# MCU.net
KiCad netlist of a schematic drawn in Altium Designer
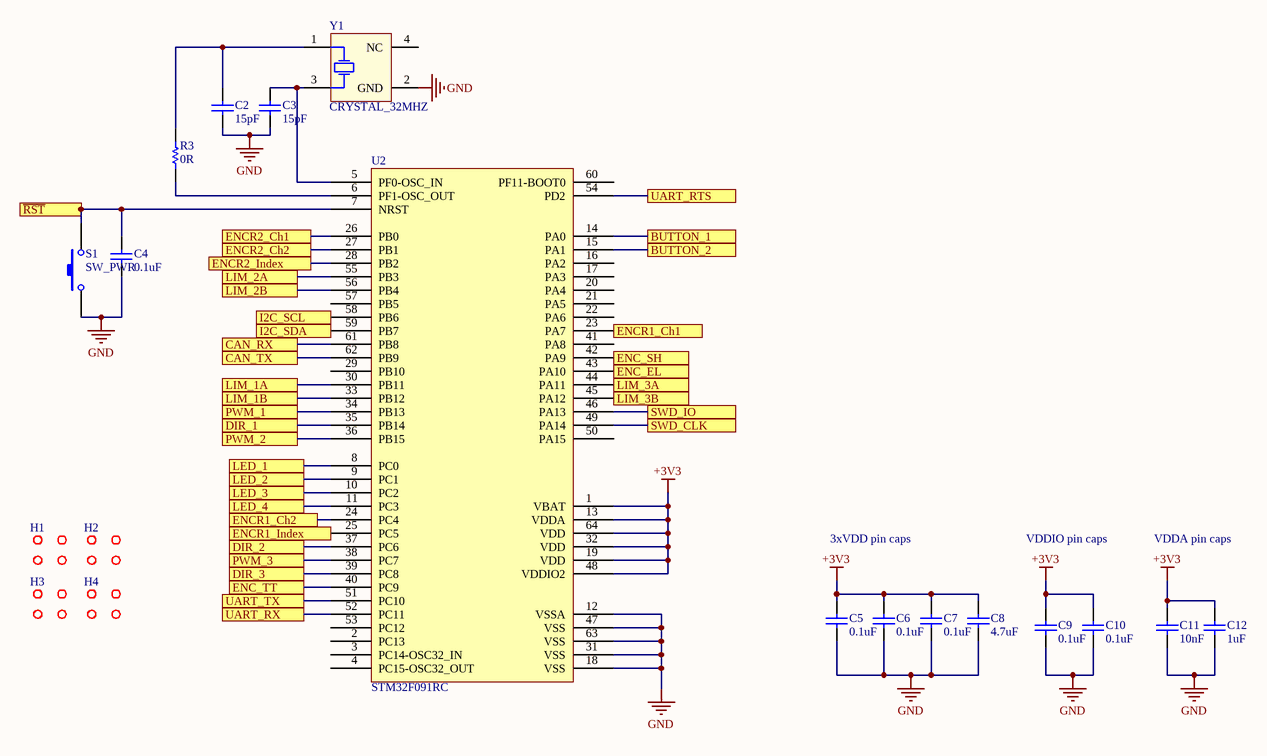
[diagram p0: MCU.SchDoc]

(export (version "E")
  (design (tool "Eeschema 10.0.6"))
  (components
    (comp (ref "C2")
      (value "15pF")
      (footprint "CAPC0603(1608)55_N")
      (description "CAP CER 15PF 250V NPO 0603")
      (fields (field (name "MANUFACTURER") "Yageo") (field (name "MPN") "AC0603JRNPOYBN150"))
      (libsource (lib "UWRT_Schematic_Library_2019") (part "CAP_15pF_0603"))
    )
    (comp (ref "C3")
      (value "15pF")
      (footprint "CAPC0603(1608)55_N")
      (description "CAP CER 15PF 250V NPO 0603")
      (fields (field (name "MANUFACTURER") "Yageo") (field (name "MPN") "AC0603JRNPOYBN150"))
      (libsource (lib "UWRT_Schematic_Library_2019") (part "CAP_15pF_0603"))
    )
    (comp (ref "C4")
      (value "0.1uF")
      (footprint "CAPC0603(1608)55_N")
      (description "CAP CER 0.1UF 16V X7R 0603")
      (fields (field (name "MANUFACTURER") "Yageo") (field (name "MPN") "CC0603KRX7R7BB104"))
      (libsource (lib "UWRT_Schematic_Library_2019") (part "CAP_0.1uF_16V_0603"))
    )
    (comp (ref "C5")
      (value "0.1uF")
      (footprint "CAPC0603(1608)55_N")
      (description "CAP CER 0.1UF 16V X7R 0603")
      (fields (field (name "MANUFACTURER") "Yageo") (field (name "MPN") "CC0603KRX7R7BB104"))
      (libsource (lib "UWRT_Schematic_Library_2019") (part "CAP_0.1uF_16V_0603"))
    )
    (comp (ref "C6")
      (value "0.1uF")
      (footprint "CAPC0603(1608)55_N")
      (description "CAP CER 0.1UF 16V X7R 0603")
      (fields (field (name "MANUFACTURER") "Yageo") (field (name "MPN") "CC0603KRX7R7BB104"))
      (libsource (lib "UWRT_Schematic_Library_2019") (part "CAP_0.1uF_16V_0603"))
    )
    (comp (ref "C7")
      (value "0.1uF")
      (footprint "CAPC0603(1608)55_N")
      (description "CAP CER 0.1UF 16V X7R 0603")
      (fields (field (name "MANUFACTURER") "Yageo") (field (name "MPN") "CC0603KRX7R7BB104"))
      (libsource (lib "UWRT_Schematic_Library_2019") (part "CAP_0.1uF_16V_0603"))
    )
    (comp (ref "C8")
      (value "4.7uF")
      (footprint "CAPC0603(1608)55_N")
      (description "CAP CER 4.7UF 6.3V X5R 0603")
      (fields (field (name "MANUFACTURER") "Yageo") (field (name "MPN") "CC0603KRX5R5BB475"))
      (libsource (lib "UWRT_Schematic_Library_2019") (part "CAP_4.7uF_0603"))
    )
    (comp (ref "C9")
      (value "0.1uF")
      (footprint "CAPC0603(1608)55_N")
      (description "CAP CER 0.1UF 16V X7R 0603")
      (fields (field (name "MANUFACTURER") "Yageo") (field (name "MPN") "CC0603KRX7R7BB104"))
      (libsource (lib "UWRT_Schematic_Library_2019") (part "CAP_0.1uF_16V_0603"))
    )
    (comp (ref "C10")
      (value "0.1uF")
      (footprint "CAPC0603(1608)55_N")
      (description "CAP CER 0.1UF 16V X7R 0603")
      (fields (field (name "MANUFACTURER") "Yageo") (field (name "MPN") "CC0603KRX7R7BB104"))
      (libsource (lib "UWRT_Schematic_Library_2019") (part "CAP_0.1uF_16V_0603"))
    )
    (comp (ref "C11")
      (value "10nF")
      (footprint "CAPC0603(1608)55_N")
      (description "CAP CER 10000PF 16V X7R 0603")
      (fields (field (name "MANUFACTURER") "Yageo") (field (name "MPN") "CC0603KRX7R7BB103"))
      (libsource (lib "UWRT_Schematic_Library_2019") (part "CAP_10nF_0603"))
    )
    (comp (ref "C12")
      (value "1uF")
      (footprint "CAPC0603(1608)55_N")
      (description "CAP CER 1UF 16V Y5V 0603")
      (fields (field (name "MANUFACTURER") "Yageo") (field (name "MPN") "CC0603ZRY5V7BB105"))
      (libsource (lib "UWRT_Schematic_Library_2019") (part "CAP_1uF_16V_0603"))
    )
    (comp (ref "H1")
      (value "MOUNTING_HOLES")
      (footprint "MOUNTING_HOLE")
      (description "6cm x 6cm")
      (libsource (lib "UWRT_Schematic_Library_2019") (part "MOUNTING_HOLES"))
    )
    (comp (ref "H2")
      (value "MOUNTING_HOLES")
      (footprint "MOUNTING_HOLE")
      (description "6cm x 6cm")
      (libsource (lib "UWRT_Schematic_Library_2019") (part "MOUNTING_HOLES"))
    )
    (comp (ref "H3")
      (value "MOUNTING_HOLES")
      (footprint "MOUNTING_HOLE")
      (description "6cm x 6cm")
      (libsource (lib "UWRT_Schematic_Library_2019") (part "MOUNTING_HOLES"))
    )
    (comp (ref "H4")
      (value "MOUNTING_HOLES")
      (footprint "MOUNTING_HOLE")
      (description "6cm x 6cm")
      (libsource (lib "UWRT_Schematic_Library_2019") (part "MOUNTING_HOLES"))
    )
    (comp (ref "R3")
      (value "0R")
      (footprint "RESC0603(1608)_N")
      (description "RES SMD 0 OHM JUMPER 1/10W 0603")
      (fields (field (name "MANUFACTURER") "Yageo") (field (name "MPN") "RC0603JR-070RL"))
      (libsource (lib "UWRT_Schematic_Library_2019") (part "RES_0R_0603"))
    )
    (comp (ref "S1")
      (value "SW_PWR")
      (footprint "PTS830GM140")
      (description "Power Switch (Red)")
      (fields
        (field (name "MPN") "PTS830GM140 SMTR LFS")
        (field (name "DIGIKEY PART NUMBER") "CKN10587CT-ND")
      )
      (libsource (lib "UWRT_Schematic_Library_2019") (part "SW_PWR"))
    )
    (comp (ref "U2")
      (value "STM32F091RC")
      (footprint "UWRT_Footprint_Library_2019:STM_LQFP64_N")
      (fields
        (field (name "MANUFACTURER") "STMicroelectronics")
        (field (name "DIGIKEY PART NUMBER") "497-15167-ND")
      )
      (libsource (lib "UWRT_Schematic_Library_2019") (part "STM32F091RC"))
    )
    (comp (ref "Y1")
      (value "CRYSTAL_32MHZ")
      (footprint "AVX-CX2520DB32000D0GEJZ1-4_V")
      (description "CRYSTAL 32MHZ 8PF SMD")
      (fields
        (field (name "MANUFACTURER") "Kyocera International Inc. Electronic Components")
        (field (name "MPN") "CX2520DB32000D0GPSC1")
      )
      (libsource (lib "UWRT_Schematic_Library_2019") (part "CRYSTAL_32MHZ"))
    )
  )
  (nets
    (net (code "1") (name "+3V3") (class "Default")
      (node (ref "C10") (pin "2") (pinfunction "2_2") (pintype "passive"))
      (node (ref "C11") (pin "2") (pinfunction "2_2") (pintype "passive"))
      (node (ref "C12") (pin "2") (pinfunction "2_2") (pintype "passive"))
      (node (ref "C5") (pin "2") (pinfunction "2_2") (pintype "passive"))
      (node (ref "C6") (pin "2") (pinfunction "2_2") (pintype "passive"))
      (node (ref "C7") (pin "2") (pinfunction "2_2") (pintype "passive"))
      (node (ref "C8") (pin "2") (pinfunction "2_2") (pintype "passive"))
      (node (ref "C9") (pin "2") (pinfunction "2_2") (pintype "passive"))
      (node (ref "U2") (pin "1") (pinfunction "VBAT_1") (pintype "passive"))
      (node (ref "U2") (pin "13") (pinfunction "VDDA_13") (pintype "passive"))
      (node (ref "U2") (pin "19") (pinfunction "VDD_19") (pintype "passive"))
      (node (ref "U2") (pin "32") (pinfunction "VDD_32") (pintype "passive"))
      (node (ref "U2") (pin "48") (pinfunction "VDDIO2_48") (pintype "passive"))
      (node (ref "U2") (pin "64") (pinfunction "VDD_64") (pintype "passive"))
    )
    (net (code "2") (name "/BUTTON_1") (class "Default")
      (node (ref "U2") (pin "14") (pinfunction "PA0_14") (pintype "passive"))
    )
    (net (code "3") (name "/BUTTON_2") (class "Default")
      (node (ref "U2") (pin "15") (pinfunction "PA1_15") (pintype "passive"))
    )
    (net (code "4") (name "/CAN_RX") (class "Default")
      (node (ref "U2") (pin "61") (pinfunction "PB8_61") (pintype "passive"))
    )
    (net (code "5") (name "/CAN_TX") (class "Default")
      (node (ref "U2") (pin "62") (pinfunction "PB9_62") (pintype "passive"))
    )
    (net (code "6") (name "/DIR_1") (class "Default")
      (node (ref "U2") (pin "35") (pinfunction "PB14_35") (pintype "passive"))
    )
    (net (code "7") (name "/DIR_2") (class "Default")
      (node (ref "U2") (pin "37") (pinfunction "PC6_37") (pintype "passive"))
    )
    (net (code "8") (name "/DIR_3") (class "Default")
      (node (ref "U2") (pin "39") (pinfunction "PC8_39") (pintype "passive"))
    )
    (net (code "9") (name "/ENCR1_Ch1") (class "Default")
      (node (ref "U2") (pin "23") (pinfunction "PA7_23") (pintype "passive"))
    )
    (net (code "10") (name "/ENCR1_Ch2") (class "Default")
      (node (ref "U2") (pin "24") (pinfunction "PC4_24") (pintype "passive"))
    )
    (net (code "11") (name "/ENCR1_Index") (class "Default")
      (node (ref "U2") (pin "25") (pinfunction "PC5_25") (pintype "passive"))
    )
    (net (code "12") (name "/ENCR2_Ch1") (class "Default")
      (node (ref "U2") (pin "26") (pinfunction "PB0_26") (pintype "passive"))
    )
    (net (code "13") (name "/ENCR2_Ch2") (class "Default")
      (node (ref "U2") (pin "27") (pinfunction "PB1_27") (pintype "passive"))
    )
    (net (code "14") (name "/ENCR2_Index") (class "Default")
      (node (ref "U2") (pin "28") (pinfunction "PB2_28") (pintype "passive"))
    )
    (net (code "15") (name "/ENC_EL") (class "Default")
      (node (ref "U2") (pin "43") (pinfunction "PA10_43") (pintype "passive"))
    )
    (net (code "16") (name "/ENC_SH") (class "Default")
      (node (ref "U2") (pin "42") (pinfunction "PA9_42") (pintype "passive"))
    )
    (net (code "17") (name "/ENC_TT") (class "Default")
      (node (ref "U2") (pin "40") (pinfunction "PC9_40") (pintype "passive"))
    )
    (net (code "18") (name "/I2C_SCL") (class "Default")
      (node (ref "U2") (pin "58") (pinfunction "PB6_58") (pintype "passive"))
    )
    (net (code "19") (name "/I2C_SDA") (class "Default")
      (node (ref "U2") (pin "59") (pinfunction "PB7_59") (pintype "passive"))
    )
    (net (code "20") (name "/LED_1") (class "Default")
      (node (ref "U2") (pin "8") (pinfunction "PC0_8") (pintype "passive"))
    )
    (net (code "21") (name "/LED_2") (class "Default")
      (node (ref "U2") (pin "9") (pinfunction "PC1_9") (pintype "passive"))
    )
    (net (code "22") (name "/LED_3") (class "Default")
      (node (ref "U2") (pin "10") (pinfunction "PC2_10") (pintype "passive"))
    )
    (net (code "23") (name "/LED_4") (class "Default")
      (node (ref "U2") (pin "11") (pinfunction "PC3_11") (pintype "passive"))
    )
    (net (code "24") (name "/LIM_1A") (class "Default")
      (node (ref "U2") (pin "30") (pinfunction "PB11_30") (pintype "passive"))
    )
    (net (code "25") (name "/LIM_1B") (class "Default")
      (node (ref "U2") (pin "33") (pinfunction "PB12_33") (pintype "passive"))
    )
    (net (code "26") (name "/LIM_2A") (class "Default")
      (node (ref "U2") (pin "55") (pinfunction "PB3_55") (pintype "passive"))
    )
    (net (code "27") (name "/LIM_2B") (class "Default")
      (node (ref "U2") (pin "56") (pinfunction "PB4_56") (pintype "passive"))
    )
    (net (code "28") (name "/LIM_3A") (class "Default")
      (node (ref "U2") (pin "44") (pinfunction "PA11_44") (pintype "passive"))
    )
    (net (code "29") (name "/LIM_3B") (class "Default")
      (node (ref "U2") (pin "45") (pinfunction "PA12_45") (pintype "passive"))
    )
    (net (code "30") (name "/PWM_1") (class "Default")
      (node (ref "U2") (pin "34") (pinfunction "PB13_34") (pintype "passive"))
    )
    (net (code "31") (name "/PWM_2") (class "Default")
      (node (ref "U2") (pin "36") (pinfunction "PB15_36") (pintype "passive"))
    )
    (net (code "32") (name "/PWM_3") (class "Default")
      (node (ref "U2") (pin "38") (pinfunction "PC7_38") (pintype "passive"))
    )
    (net (code "33") (name "/SWD_CLK") (class "Default")
      (node (ref "U2") (pin "49") (pinfunction "PA14_49") (pintype "passive"))
    )
    (net (code "34") (name "/SWD_IO") (class "Default")
      (node (ref "U2") (pin "46") (pinfunction "PA13_46") (pintype "passive"))
    )
    (net (code "35") (name "/UART_RTS") (class "Default")
      (node (ref "U2") (pin "54") (pinfunction "PD2_54") (pintype "passive"))
    )
    (net (code "36") (name "/UART_RX") (class "Default")
      (node (ref "U2") (pin "52") (pinfunction "PC11_52") (pintype "passive"))
    )
    (net (code "37") (name "/UART_TX") (class "Default")
      (node (ref "U2") (pin "51") (pinfunction "PC10_51") (pintype "passive"))
    )
    (net (code "38") (name "/~{RST}") (class "Default")
      (node (ref "C4") (pin "2") (pinfunction "2_2") (pintype "passive"))
      (node (ref "S1") (pin "2") (pinfunction "2_2") (pintype "passive"))
      (node (ref "U2") (pin "7") (pinfunction "NRST_7") (pintype "passive"))
    )
    (net (code "39") (name "GND") (class "Default")
      (node (ref "C10") (pin "1") (pinfunction "1_1") (pintype "passive"))
      (node (ref "C11") (pin "1") (pinfunction "1_1") (pintype "passive"))
      (node (ref "C12") (pin "1") (pinfunction "1_1") (pintype "passive"))
      (node (ref "C2") (pin "1") (pinfunction "1_1") (pintype "passive"))
      (node (ref "C3") (pin "1") (pinfunction "1_1") (pintype "passive"))
      (node (ref "C4") (pin "1") (pinfunction "1_1") (pintype "passive"))
      (node (ref "C5") (pin "1") (pinfunction "1_1") (pintype "passive"))
      (node (ref "C6") (pin "1") (pinfunction "1_1") (pintype "passive"))
      (node (ref "C7") (pin "1") (pinfunction "1_1") (pintype "passive"))
      (node (ref "C8") (pin "1") (pinfunction "1_1") (pintype "passive"))
      (node (ref "C9") (pin "1") (pinfunction "1_1") (pintype "passive"))
      (node (ref "S1") (pin "1") (pinfunction "1_1") (pintype "passive"))
      (node (ref "U2") (pin "12") (pinfunction "VSSA_12") (pintype "passive"))
      (node (ref "U2") (pin "18") (pinfunction "VSS_18") (pintype "passive"))
      (node (ref "U2") (pin "31") (pinfunction "VSS_31") (pintype "passive"))
      (node (ref "U2") (pin "47") (pinfunction "VSS_47") (pintype "passive"))
      (node (ref "U2") (pin "63") (pinfunction "VSS_63") (pintype "passive"))
      (node (ref "Y1") (pin "2") (pinfunction "GND_2") (pintype "power_in"))
    )
    (net (code "40") (name "Net-(C2-Pad2)") (class "Default")
      (node (ref "C2") (pin "2") (pinfunction "2_2") (pintype "passive"))
      (node (ref "R3") (pin "2") (pinfunction "2_2") (pintype "passive"))
      (node (ref "Y1") (pin "1") (pinfunction "HOT_1") (pintype "passive"))
    )
    (net (code "41") (name "Net-(U2-PF0-OSC_IN)") (class "Default")
      (node (ref "C3") (pin "2") (pinfunction "2_2") (pintype "passive"))
      (node (ref "U2") (pin "5") (pinfunction "PF0-OSC_IN_5") (pintype "passive"))
      (node (ref "Y1") (pin "3") (pinfunction "HOT_3") (pintype "passive"))
    )
    (net (code "42") (name "Net-(U2-PF1-OSC_OUT)") (class "Default")
      (node (ref "R3") (pin "1") (pinfunction "1_1") (pintype "passive"))
      (node (ref "U2") (pin "6") (pinfunction "PF1-OSC_OUT_6") (pintype "passive"))
    )
    (net (code "43") (name "unconnected-(U2-PA2-Pad16)") (class "Default")
      (node (ref "U2") (pin "16") (pinfunction "PA2_16") (pintype "passive"))
    )
    (net (code "44") (name "unconnected-(U2-PA3-Pad17)") (class "Default")
      (node (ref "U2") (pin "17") (pinfunction "PA3_17") (pintype "passive"))
    )
    (net (code "45") (name "unconnected-(U2-PA4-Pad20)") (class "Default")
      (node (ref "U2") (pin "20") (pinfunction "PA4_20") (pintype "passive"))
    )
    (net (code "46") (name "unconnected-(U2-PA5-Pad21)") (class "Default")
      (node (ref "U2") (pin "21") (pinfunction "PA5_21") (pintype "passive"))
    )
    (net (code "47") (name "unconnected-(U2-PA6-Pad22)") (class "Default")
      (node (ref "U2") (pin "22") (pinfunction "PA6_22") (pintype "passive"))
    )
    (net (code "48") (name "unconnected-(U2-PA8-Pad41)") (class "Default")
      (node (ref "U2") (pin "41") (pinfunction "PA8_41") (pintype "passive"))
    )
    (net (code "49") (name "unconnected-(U2-PA15-Pad50)") (class "Default")
      (node (ref "U2") (pin "50") (pinfunction "PA15_50") (pintype "passive"))
    )
    (net (code "50") (name "unconnected-(U2-PB5-Pad57)") (class "Default")
      (node (ref "U2") (pin "57") (pinfunction "PB5_57") (pintype "passive"))
    )
    (net (code "51") (name "unconnected-(U2-PB10-Pad29)") (class "Default")
      (node (ref "U2") (pin "29") (pinfunction "PB10_29") (pintype "passive"))
    )
    (net (code "52") (name "unconnected-(U2-PC12-Pad53)") (class "Default")
      (node (ref "U2") (pin "53") (pinfunction "PC12_53") (pintype "passive"))
    )
    (net (code "53") (name "unconnected-(U2-PC13-Pad2)") (class "Default")
      (node (ref "U2") (pin "2") (pinfunction "PC13_2") (pintype "passive"))
    )
    (net (code "54") (name "unconnected-(U2-PC14-OSC32_IN-Pad3)") (class "Default")
      (node (ref "U2") (pin "3") (pinfunction "PC14-OSC32_IN_3") (pintype "passive"))
    )
    (net (code "55") (name "unconnected-(U2-PC15-OSC32_OUT-Pad4)") (class "Default")
      (node (ref "U2") (pin "4") (pinfunction "PC15-OSC32_OUT_4") (pintype "passive"))
    )
    (net (code "56") (name "unconnected-(U2-PF11-BOOT0-Pad60)") (class "Default")
      (node (ref "U2") (pin "60") (pinfunction "PF11-BOOT0_60") (pintype "passive"))
    )
    (net (code "57") (name "unconnected-(Y1-NC-Pad4)") (class "Default")
      (node (ref "Y1") (pin "4") (pinfunction "NC_4") (pintype "passive"))
    )
  )
)
